# 001.net
KiCad netlist of a schematic drawn in EAGLE
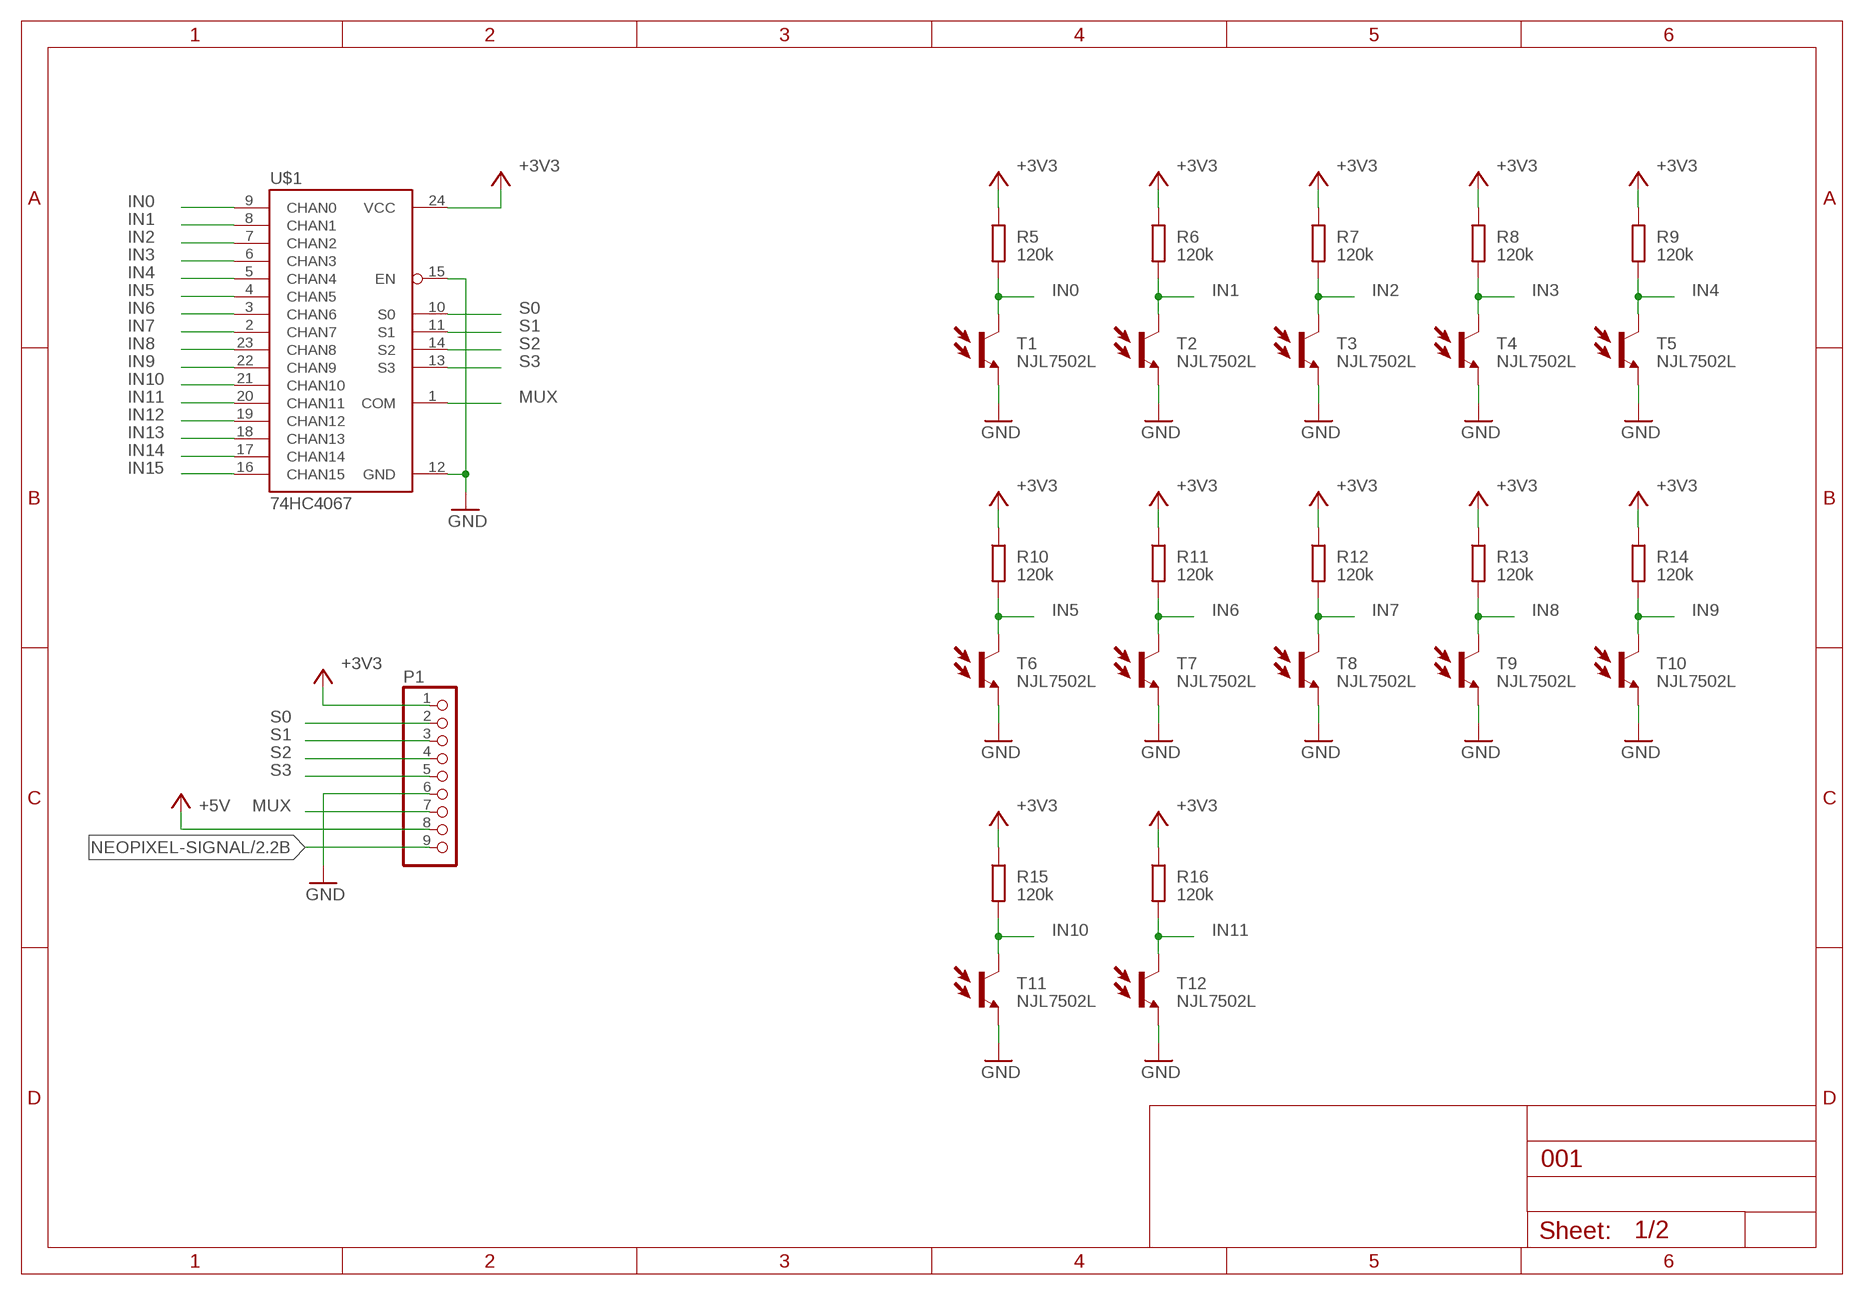
[diagram p0: schematic, sheet 1]
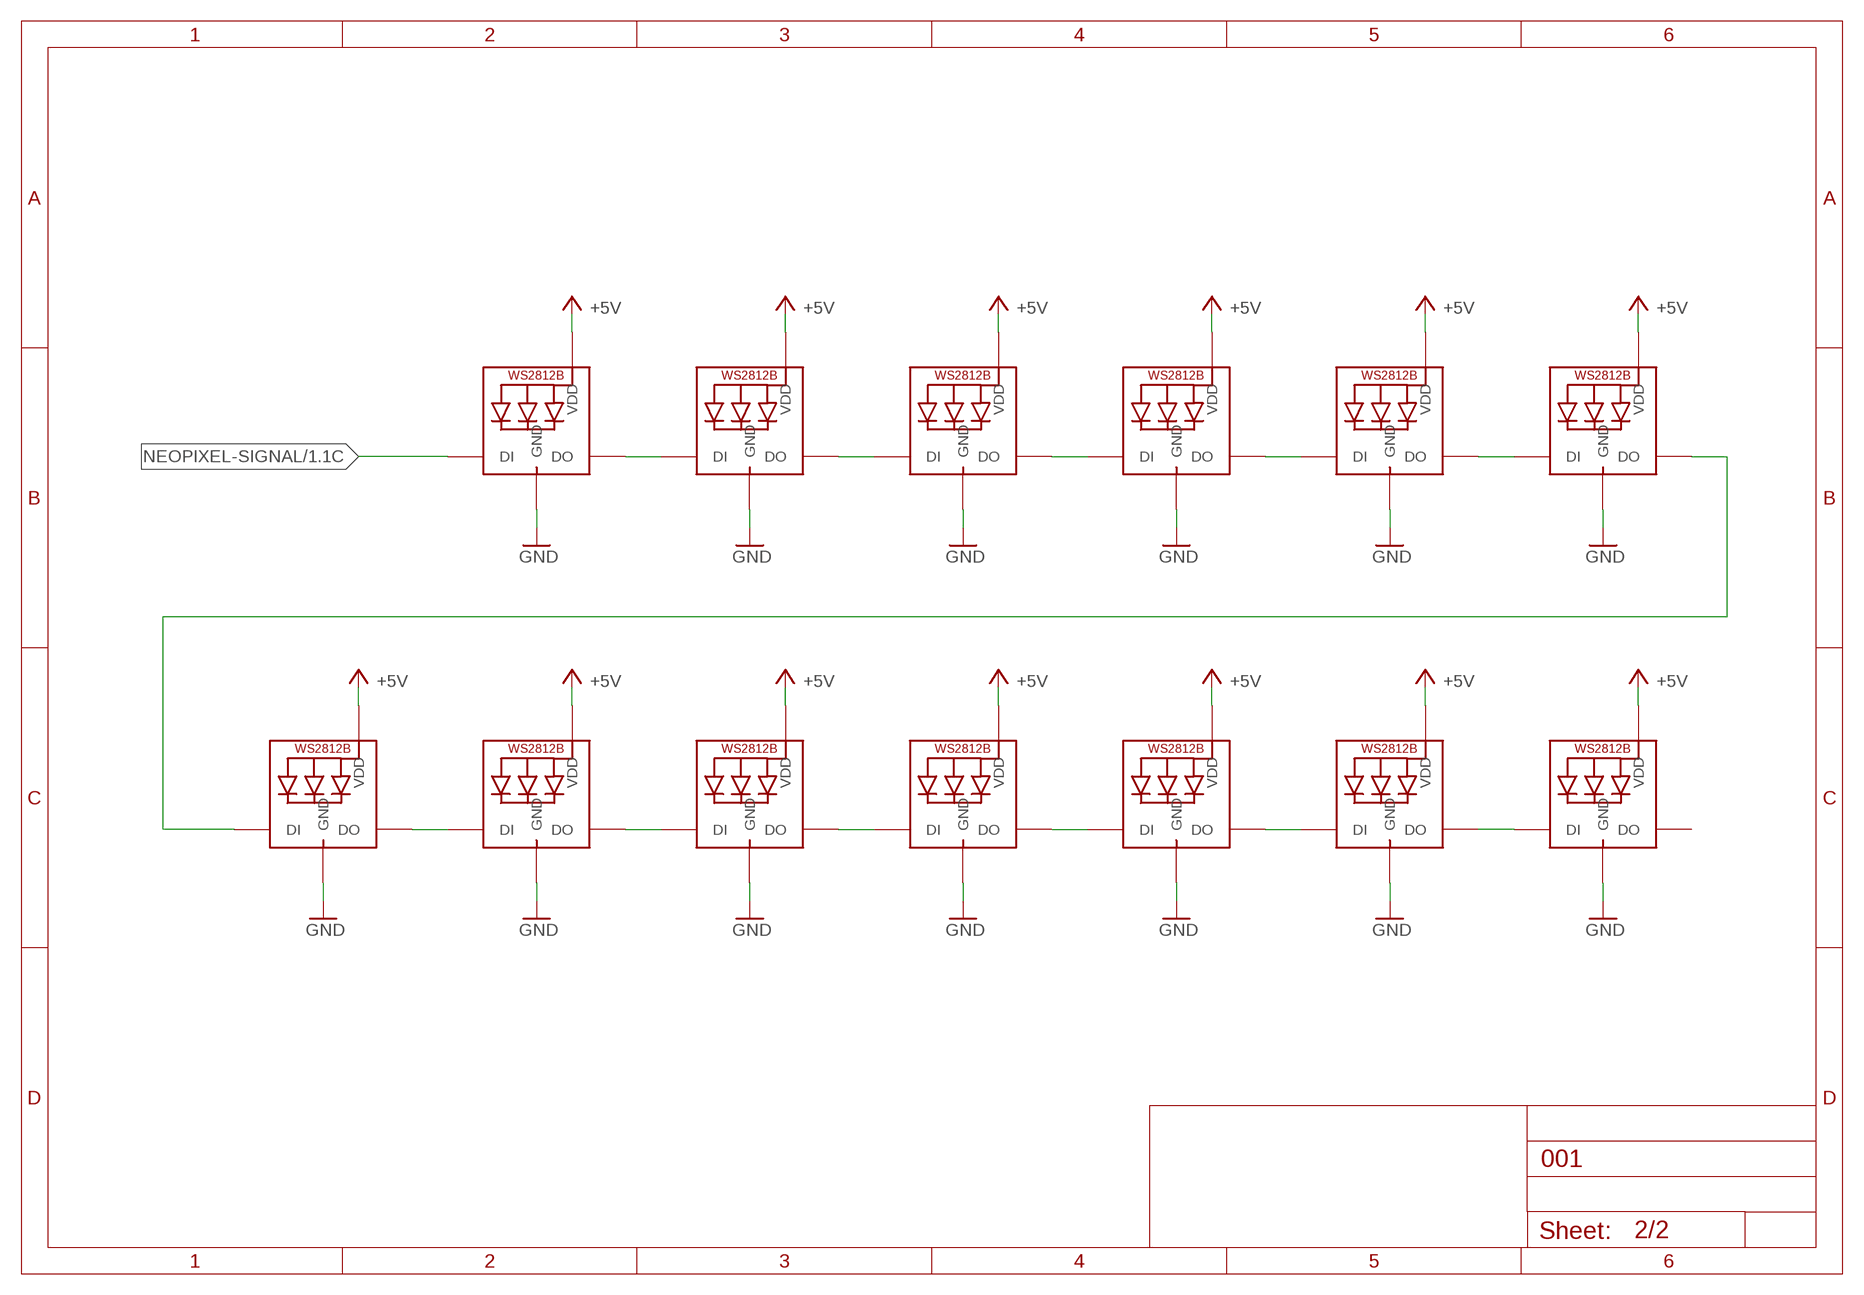
[diagram p1: schematic, sheet 2]

(export (version "E")
  (design (tool "Eeschema 10.0.6"))
  (components
    (comp (ref "LED1")
      (value "WS2812B5050")
      (footprint "eagle-import:WS2812B")
      (libsource (lib "eagle-import") (part "WS2812B5050"))
    )
    (comp (ref "LED2")
      (value "WS2812B5050")
      (footprint "eagle-import:WS2812B")
      (libsource (lib "eagle-import") (part "WS2812B5050"))
    )
    (comp (ref "LED3")
      (value "WS2812B5050")
      (footprint "eagle-import:WS2812B")
      (libsource (lib "eagle-import") (part "WS2812B5050"))
    )
    (comp (ref "LED4")
      (value "WS2812B5050")
      (footprint "eagle-import:WS2812B")
      (libsource (lib "eagle-import") (part "WS2812B5050"))
    )
    (comp (ref "LED5")
      (value "WS2812B5050")
      (footprint "eagle-import:WS2812B")
      (libsource (lib "eagle-import") (part "WS2812B5050"))
    )
    (comp (ref "LED6")
      (value "WS2812B5050")
      (footprint "eagle-import:WS2812B")
      (libsource (lib "eagle-import") (part "WS2812B5050"))
    )
    (comp (ref "LED7")
      (value "WS2812B5050")
      (footprint "eagle-import:WS2812B")
      (libsource (lib "eagle-import") (part "WS2812B5050"))
    )
    (comp (ref "LED8")
      (value "WS2812B5050")
      (footprint "eagle-import:WS2812B")
      (libsource (lib "eagle-import") (part "WS2812B5050"))
    )
    (comp (ref "LED9")
      (value "WS2812B5050")
      (footprint "eagle-import:WS2812B")
      (libsource (lib "eagle-import") (part "WS2812B5050"))
    )
    (comp (ref "LED10")
      (value "WS2812B5050")
      (footprint "eagle-import:WS2812B")
      (libsource (lib "eagle-import") (part "WS2812B5050"))
    )
    (comp (ref "LED11")
      (value "WS2812B5050")
      (footprint "eagle-import:WS2812B")
      (libsource (lib "eagle-import") (part "WS2812B5050"))
    )
    (comp (ref "LED12")
      (value "WS2812B5050")
      (footprint "eagle-import:WS2812B")
      (libsource (lib "eagle-import") (part "WS2812B5050"))
    )
    (comp (ref "LED13")
      (value "WS2812B5050")
      (footprint "eagle-import:WS2812B")
      (libsource (lib "eagle-import") (part "WS2812B5050"))
    )
    (comp (ref "P1")
      (value "S9B-ZR-SM4A-TF")
      (footprint "eagle-import:ZH-SM4-SIDE09")
      (libsource (lib "eagle-import") (part "S9B-ZR-SM4A-TF"))
    )
    (comp (ref "R5")
      (value "120k")
      (footprint "eagle-import:R0805")
      (libsource (lib "eagle-import") (part "R-EU_R0805"))
    )
    (comp (ref "R6")
      (value "120k")
      (footprint "eagle-import:R0805")
      (libsource (lib "eagle-import") (part "R-EU_R0805"))
    )
    (comp (ref "R7")
      (value "120k")
      (footprint "eagle-import:R0805")
      (libsource (lib "eagle-import") (part "R-EU_R0805"))
    )
    (comp (ref "R8")
      (value "120k")
      (footprint "eagle-import:R0805")
      (libsource (lib "eagle-import") (part "R-EU_R0805"))
    )
    (comp (ref "R9")
      (value "120k")
      (footprint "eagle-import:R0805")
      (libsource (lib "eagle-import") (part "R-EU_R0805"))
    )
    (comp (ref "R10")
      (value "120k")
      (footprint "eagle-import:R0805")
      (libsource (lib "eagle-import") (part "R-EU_R0805"))
    )
    (comp (ref "R11")
      (value "120k")
      (footprint "eagle-import:R0805")
      (libsource (lib "eagle-import") (part "R-EU_R0805"))
    )
    (comp (ref "R12")
      (value "120k")
      (footprint "eagle-import:R0805")
      (libsource (lib "eagle-import") (part "R-EU_R0805"))
    )
    (comp (ref "R13")
      (value "120k")
      (footprint "eagle-import:R0805")
      (libsource (lib "eagle-import") (part "R-EU_R0805"))
    )
    (comp (ref "R14")
      (value "120k")
      (footprint "eagle-import:R0805")
      (libsource (lib "eagle-import") (part "R-EU_R0805"))
    )
    (comp (ref "R15")
      (value "120k")
      (footprint "eagle-import:R0805")
      (libsource (lib "eagle-import") (part "R-EU_R0805"))
    )
    (comp (ref "R16")
      (value "120k")
      (footprint "eagle-import:R0805")
      (libsource (lib "eagle-import") (part "R-EU_R0805"))
    )
    (comp (ref "T1")
      (value "NJL7502L")
      (footprint "eagle-import:MYPARTS_NJL7502L")
      (libsource (lib "eagle-import") (part "MYPARTS_NJL7502L"))
    )
    (comp (ref "T2")
      (value "NJL7502L")
      (footprint "eagle-import:MYPARTS_NJL7502L")
      (libsource (lib "eagle-import") (part "MYPARTS_NJL7502L"))
    )
    (comp (ref "T3")
      (value "NJL7502L")
      (footprint "eagle-import:MYPARTS_NJL7502L")
      (libsource (lib "eagle-import") (part "MYPARTS_NJL7502L"))
    )
    (comp (ref "T4")
      (value "NJL7502L")
      (footprint "eagle-import:MYPARTS_NJL7502L")
      (libsource (lib "eagle-import") (part "MYPARTS_NJL7502L"))
    )
    (comp (ref "T5")
      (value "NJL7502L")
      (footprint "eagle-import:MYPARTS_NJL7502L")
      (libsource (lib "eagle-import") (part "MYPARTS_NJL7502L"))
    )
    (comp (ref "T6")
      (value "NJL7502L")
      (footprint "eagle-import:MYPARTS_NJL7502L")
      (libsource (lib "eagle-import") (part "MYPARTS_NJL7502L"))
    )
    (comp (ref "T7")
      (value "NJL7502L")
      (footprint "eagle-import:MYPARTS_NJL7502L")
      (libsource (lib "eagle-import") (part "MYPARTS_NJL7502L"))
    )
    (comp (ref "T8")
      (value "NJL7502L")
      (footprint "eagle-import:MYPARTS_NJL7502L")
      (libsource (lib "eagle-import") (part "MYPARTS_NJL7502L"))
    )
    (comp (ref "T9")
      (value "NJL7502L")
      (footprint "eagle-import:MYPARTS_NJL7502L")
      (libsource (lib "eagle-import") (part "MYPARTS_NJL7502L"))
    )
    (comp (ref "T10")
      (value "NJL7502L")
      (footprint "eagle-import:MYPARTS_NJL7502L")
      (libsource (lib "eagle-import") (part "MYPARTS_NJL7502L"))
    )
    (comp (ref "T11")
      (value "NJL7502L")
      (footprint "eagle-import:MYPARTS_NJL7502L")
      (libsource (lib "eagle-import") (part "MYPARTS_NJL7502L"))
    )
    (comp (ref "T12")
      (value "NJL7502L")
      (footprint "eagle-import:MYPARTS_NJL7502L")
      (libsource (lib "eagle-import") (part "MYPARTS_NJL7502L"))
    )
    (comp (ref "U$1")
      (value "74HC4067")
      (footprint "eagle-import:SPARKFUN_SSOP24")
      (libsource (lib "eagle-import") (part "SPARKFUN_MUX-74HC4067SMD"))
    )
  )
  (nets
    (net (code "1") (name "+3V3") (class "Default")
      (node (ref "P1") (pin "1") (pinfunction "1_1") (pintype "passive"))
      (node (ref "R10") (pin "1") (pinfunction "1_1") (pintype "passive"))
      (node (ref "R11") (pin "1") (pinfunction "1_1") (pintype "passive"))
      (node (ref "R12") (pin "1") (pinfunction "1_1") (pintype "passive"))
      (node (ref "R13") (pin "1") (pinfunction "1_1") (pintype "passive"))
      (node (ref "R14") (pin "1") (pinfunction "1_1") (pintype "passive"))
      (node (ref "R15") (pin "1") (pinfunction "1_1") (pintype "passive"))
      (node (ref "R16") (pin "1") (pinfunction "1_1") (pintype "passive"))
      (node (ref "R5") (pin "1") (pinfunction "1_1") (pintype "passive"))
      (node (ref "R6") (pin "1") (pinfunction "1_1") (pintype "passive"))
      (node (ref "R7") (pin "1") (pinfunction "1_1") (pintype "passive"))
      (node (ref "R8") (pin "1") (pinfunction "1_1") (pintype "passive"))
      (node (ref "R9") (pin "1") (pinfunction "1_1") (pintype "passive"))
      (node (ref "U$1") (pin "24") (pinfunction "VCC_24") (pintype "bidirectional"))
    )
    (net (code "2") (name "+5V") (class "Default")
      (node (ref "LED1") (pin "1-VDD") (pinfunction "VDD_1-VDD") (pintype "power_in"))
      (node (ref "LED10") (pin "1-VDD") (pinfunction "VDD_1-VDD") (pintype "power_in"))
      (node (ref "LED11") (pin "1-VDD") (pinfunction "VDD_1-VDD") (pintype "power_in"))
      (node (ref "LED12") (pin "1-VDD") (pinfunction "VDD_1-VDD") (pintype "power_in"))
      (node (ref "LED13") (pin "1-VDD") (pinfunction "VDD_1-VDD") (pintype "power_in"))
      (node (ref "LED2") (pin "1-VDD") (pinfunction "VDD_1-VDD") (pintype "power_in"))
      (node (ref "LED3") (pin "1-VDD") (pinfunction "VDD_1-VDD") (pintype "power_in"))
      (node (ref "LED4") (pin "1-VDD") (pinfunction "VDD_1-VDD") (pintype "power_in"))
      (node (ref "LED5") (pin "1-VDD") (pinfunction "VDD_1-VDD") (pintype "power_in"))
      (node (ref "LED6") (pin "1-VDD") (pinfunction "VDD_1-VDD") (pintype "power_in"))
      (node (ref "LED7") (pin "1-VDD") (pinfunction "VDD_1-VDD") (pintype "power_in"))
      (node (ref "LED8") (pin "1-VDD") (pinfunction "VDD_1-VDD") (pintype "power_in"))
      (node (ref "LED9") (pin "1-VDD") (pinfunction "VDD_1-VDD") (pintype "power_in"))
      (node (ref "P1") (pin "8") (pinfunction "8_8") (pintype "passive"))
    )
    (net (code "3") (name "GND") (class "Default")
      (node (ref "LED1") (pin "3-GND") (pinfunction "GND_3-GND") (pintype "power_in"))
      (node (ref "LED10") (pin "3-GND") (pinfunction "GND_3-GND") (pintype "power_in"))
      (node (ref "LED11") (pin "3-GND") (pinfunction "GND_3-GND") (pintype "power_in"))
      (node (ref "LED12") (pin "3-GND") (pinfunction "GND_3-GND") (pintype "power_in"))
      (node (ref "LED13") (pin "3-GND") (pinfunction "GND_3-GND") (pintype "power_in"))
      (node (ref "LED2") (pin "3-GND") (pinfunction "GND_3-GND") (pintype "power_in"))
      (node (ref "LED3") (pin "3-GND") (pinfunction "GND_3-GND") (pintype "power_in"))
      (node (ref "LED4") (pin "3-GND") (pinfunction "GND_3-GND") (pintype "power_in"))
      (node (ref "LED5") (pin "3-GND") (pinfunction "GND_3-GND") (pintype "power_in"))
      (node (ref "LED6") (pin "3-GND") (pinfunction "GND_3-GND") (pintype "power_in"))
      (node (ref "LED7") (pin "3-GND") (pinfunction "GND_3-GND") (pintype "power_in"))
      (node (ref "LED8") (pin "3-GND") (pinfunction "GND_3-GND") (pintype "power_in"))
      (node (ref "LED9") (pin "3-GND") (pinfunction "GND_3-GND") (pintype "power_in"))
      (node (ref "P1") (pin "6") (pinfunction "6_6") (pintype "passive"))
      (node (ref "T1") (pin "E") (pinfunction "E_E") (pintype "passive"))
      (node (ref "T10") (pin "E") (pinfunction "E_E") (pintype "passive"))
      (node (ref "T11") (pin "E") (pinfunction "E_E") (pintype "passive"))
      (node (ref "T12") (pin "E") (pinfunction "E_E") (pintype "passive"))
      (node (ref "T2") (pin "E") (pinfunction "E_E") (pintype "passive"))
      (node (ref "T3") (pin "E") (pinfunction "E_E") (pintype "passive"))
      (node (ref "T4") (pin "E") (pinfunction "E_E") (pintype "passive"))
      (node (ref "T5") (pin "E") (pinfunction "E_E") (pintype "passive"))
      (node (ref "T6") (pin "E") (pinfunction "E_E") (pintype "passive"))
      (node (ref "T7") (pin "E") (pinfunction "E_E") (pintype "passive"))
      (node (ref "T8") (pin "E") (pinfunction "E_E") (pintype "passive"))
      (node (ref "T9") (pin "E") (pinfunction "E_E") (pintype "passive"))
      (node (ref "U$1") (pin "12") (pinfunction "GND_12") (pintype "bidirectional"))
      (node (ref "U$1") (pin "15") (pinfunction "EN_15") (pintype "input"))
    )
    (net (code "4") (name "IN0") (class "Default")
      (node (ref "R5") (pin "2") (pinfunction "2_2") (pintype "passive"))
      (node (ref "T1") (pin "C") (pinfunction "C_C") (pintype "passive"))
      (node (ref "U$1") (pin "9") (pinfunction "CHAN0_9") (pintype "bidirectional"))
    )
    (net (code "5") (name "IN1") (class "Default")
      (node (ref "R6") (pin "2") (pinfunction "2_2") (pintype "passive"))
      (node (ref "T2") (pin "C") (pinfunction "C_C") (pintype "passive"))
      (node (ref "U$1") (pin "8") (pinfunction "CHAN1_8") (pintype "bidirectional"))
    )
    (net (code "6") (name "IN2") (class "Default")
      (node (ref "R7") (pin "2") (pinfunction "2_2") (pintype "passive"))
      (node (ref "T3") (pin "C") (pinfunction "C_C") (pintype "passive"))
      (node (ref "U$1") (pin "7") (pinfunction "CHAN2_7") (pintype "bidirectional"))
    )
    (net (code "7") (name "IN3") (class "Default")
      (node (ref "R8") (pin "2") (pinfunction "2_2") (pintype "passive"))
      (node (ref "T4") (pin "C") (pinfunction "C_C") (pintype "passive"))
      (node (ref "U$1") (pin "6") (pinfunction "CHAN3_6") (pintype "bidirectional"))
    )
    (net (code "8") (name "IN4") (class "Default")
      (node (ref "R9") (pin "2") (pinfunction "2_2") (pintype "passive"))
      (node (ref "T5") (pin "C") (pinfunction "C_C") (pintype "passive"))
      (node (ref "U$1") (pin "5") (pinfunction "CHAN4_5") (pintype "bidirectional"))
    )
    (net (code "9") (name "IN5") (class "Default")
      (node (ref "R10") (pin "2") (pinfunction "2_2") (pintype "passive"))
      (node (ref "T6") (pin "C") (pinfunction "C_C") (pintype "passive"))
      (node (ref "U$1") (pin "4") (pinfunction "CHAN5_4") (pintype "bidirectional"))
    )
    (net (code "10") (name "IN6") (class "Default")
      (node (ref "R11") (pin "2") (pinfunction "2_2") (pintype "passive"))
      (node (ref "T7") (pin "C") (pinfunction "C_C") (pintype "passive"))
      (node (ref "U$1") (pin "3") (pinfunction "CHAN6_3") (pintype "bidirectional"))
    )
    (net (code "11") (name "IN7") (class "Default")
      (node (ref "R12") (pin "2") (pinfunction "2_2") (pintype "passive"))
      (node (ref "T8") (pin "C") (pinfunction "C_C") (pintype "passive"))
      (node (ref "U$1") (pin "2") (pinfunction "CHAN7_2") (pintype "bidirectional"))
    )
    (net (code "12") (name "IN8") (class "Default")
      (node (ref "R13") (pin "2") (pinfunction "2_2") (pintype "passive"))
      (node (ref "T9") (pin "C") (pinfunction "C_C") (pintype "passive"))
      (node (ref "U$1") (pin "23") (pinfunction "CHAN8_23") (pintype "bidirectional"))
    )
    (net (code "13") (name "IN9") (class "Default")
      (node (ref "R14") (pin "2") (pinfunction "2_2") (pintype "passive"))
      (node (ref "T10") (pin "C") (pinfunction "C_C") (pintype "passive"))
      (node (ref "U$1") (pin "22") (pinfunction "CHAN9_22") (pintype "bidirectional"))
    )
    (net (code "14") (name "IN10") (class "Default")
      (node (ref "R15") (pin "2") (pinfunction "2_2") (pintype "passive"))
      (node (ref "T11") (pin "C") (pinfunction "C_C") (pintype "passive"))
      (node (ref "U$1") (pin "21") (pinfunction "CHAN10_21") (pintype "bidirectional"))
    )
    (net (code "15") (name "IN11") (class "Default")
      (node (ref "R16") (pin "2") (pinfunction "2_2") (pintype "passive"))
      (node (ref "T12") (pin "C") (pinfunction "C_C") (pintype "passive"))
      (node (ref "U$1") (pin "20") (pinfunction "CHAN11_20") (pintype "bidirectional"))
    )
    (net (code "16") (name "IN12") (class "Default")
      (node (ref "U$1") (pin "19") (pinfunction "CHAN12_19") (pintype "bidirectional"))
    )
    (net (code "17") (name "IN13") (class "Default")
      (node (ref "U$1") (pin "18") (pinfunction "CHAN13_18") (pintype "bidirectional"))
    )
    (net (code "18") (name "IN14") (class "Default")
      (node (ref "U$1") (pin "17") (pinfunction "CHAN14_17") (pintype "bidirectional"))
    )
    (net (code "19") (name "IN15") (class "Default")
      (node (ref "U$1") (pin "16") (pinfunction "CHAN15_16") (pintype "bidirectional"))
    )
    (net (code "20") (name "MUX") (class "Default")
      (node (ref "P1") (pin "7") (pinfunction "7_7") (pintype "passive"))
      (node (ref "U$1") (pin "1") (pinfunction "COM_1") (pintype "bidirectional"))
    )
    (net (code "21") (name "NEOPIXEL-SIGNAL") (class "Default")
      (node (ref "LED1") (pin "4-DIN") (pinfunction "DI_4-DIN") (pintype "input"))
      (node (ref "P1") (pin "9") (pinfunction "9_9") (pintype "passive"))
    )
    (net (code "22") (name "Net-(LED1-DO)") (class "Default")
      (node (ref "LED1") (pin "2-DOUT") (pinfunction "DO_2-DOUT") (pintype "output"))
      (node (ref "LED2") (pin "4-DIN") (pinfunction "DI_4-DIN") (pintype "input"))
    )
    (net (code "23") (name "Net-(LED2-DO)") (class "Default")
      (node (ref "LED2") (pin "2-DOUT") (pinfunction "DO_2-DOUT") (pintype "output"))
      (node (ref "LED3") (pin "4-DIN") (pinfunction "DI_4-DIN") (pintype "input"))
    )
    (net (code "24") (name "Net-(LED3-DO)") (class "Default")
      (node (ref "LED3") (pin "2-DOUT") (pinfunction "DO_2-DOUT") (pintype "output"))
      (node (ref "LED4") (pin "4-DIN") (pinfunction "DI_4-DIN") (pintype "input"))
    )
    (net (code "25") (name "Net-(LED4-DO)") (class "Default")
      (node (ref "LED4") (pin "2-DOUT") (pinfunction "DO_2-DOUT") (pintype "output"))
      (node (ref "LED5") (pin "4-DIN") (pinfunction "DI_4-DIN") (pintype "input"))
    )
    (net (code "26") (name "Net-(LED5-DO)") (class "Default")
      (node (ref "LED5") (pin "2-DOUT") (pinfunction "DO_2-DOUT") (pintype "output"))
      (node (ref "LED6") (pin "4-DIN") (pinfunction "DI_4-DIN") (pintype "input"))
    )
    (net (code "27") (name "Net-(LED6-DO)") (class "Default")
      (node (ref "LED6") (pin "2-DOUT") (pinfunction "DO_2-DOUT") (pintype "output"))
      (node (ref "LED7") (pin "4-DIN") (pinfunction "DI_4-DIN") (pintype "input"))
    )
    (net (code "28") (name "Net-(LED7-DO)") (class "Default")
      (node (ref "LED7") (pin "2-DOUT") (pinfunction "DO_2-DOUT") (pintype "output"))
      (node (ref "LED8") (pin "4-DIN") (pinfunction "DI_4-DIN") (pintype "input"))
    )
    (net (code "29") (name "Net-(LED8-DO)") (class "Default")
      (node (ref "LED8") (pin "2-DOUT") (pinfunction "DO_2-DOUT") (pintype "output"))
      (node (ref "LED9") (pin "4-DIN") (pinfunction "DI_4-DIN") (pintype "input"))
    )
    (net (code "30") (name "Net-(LED10-DI)") (class "Default")
      (node (ref "LED10") (pin "4-DIN") (pinfunction "DI_4-DIN") (pintype "input"))
      (node (ref "LED9") (pin "2-DOUT") (pinfunction "DO_2-DOUT") (pintype "output"))
    )
    (net (code "31") (name "Net-(LED10-DO)") (class "Default")
      (node (ref "LED10") (pin "2-DOUT") (pinfunction "DO_2-DOUT") (pintype "output"))
      (node (ref "LED11") (pin "4-DIN") (pinfunction "DI_4-DIN") (pintype "input"))
    )
    (net (code "32") (name "Net-(LED11-DO)") (class "Default")
      (node (ref "LED11") (pin "2-DOUT") (pinfunction "DO_2-DOUT") (pintype "output"))
      (node (ref "LED12") (pin "4-DIN") (pinfunction "DI_4-DIN") (pintype "input"))
    )
    (net (code "33") (name "Net-(LED12-DO)") (class "Default")
      (node (ref "LED12") (pin "2-DOUT") (pinfunction "DO_2-DOUT") (pintype "output"))
      (node (ref "LED13") (pin "4-DIN") (pinfunction "DI_4-DIN") (pintype "input"))
    )
    (net (code "34") (name "S0") (class "Default")
      (node (ref "P1") (pin "2") (pinfunction "2_2") (pintype "passive"))
      (node (ref "U$1") (pin "10") (pinfunction "S0_10") (pintype "input"))
    )
    (net (code "35") (name "S1") (class "Default")
      (node (ref "P1") (pin "3") (pinfunction "3_3") (pintype "passive"))
      (node (ref "U$1") (pin "11") (pinfunction "S1_11") (pintype "input"))
    )
    (net (code "36") (name "S2") (class "Default")
      (node (ref "P1") (pin "4") (pinfunction "4_4") (pintype "passive"))
      (node (ref "U$1") (pin "14") (pinfunction "S2_14") (pintype "input"))
    )
    (net (code "37") (name "S3") (class "Default")
      (node (ref "P1") (pin "5") (pinfunction "5_5") (pintype "passive"))
      (node (ref "U$1") (pin "13") (pinfunction "S3_13") (pintype "input"))
    )
    (net (code "38") (name "unconnected-(LED13-DO-Pad2-DOUT)") (class "Default")
      (node (ref "LED13") (pin "2-DOUT") (pinfunction "DO_2-DOUT") (pintype "output"))
    )
  )
)
